# HDMI.net
KiCad netlist of a schematic drawn in Altium Designer
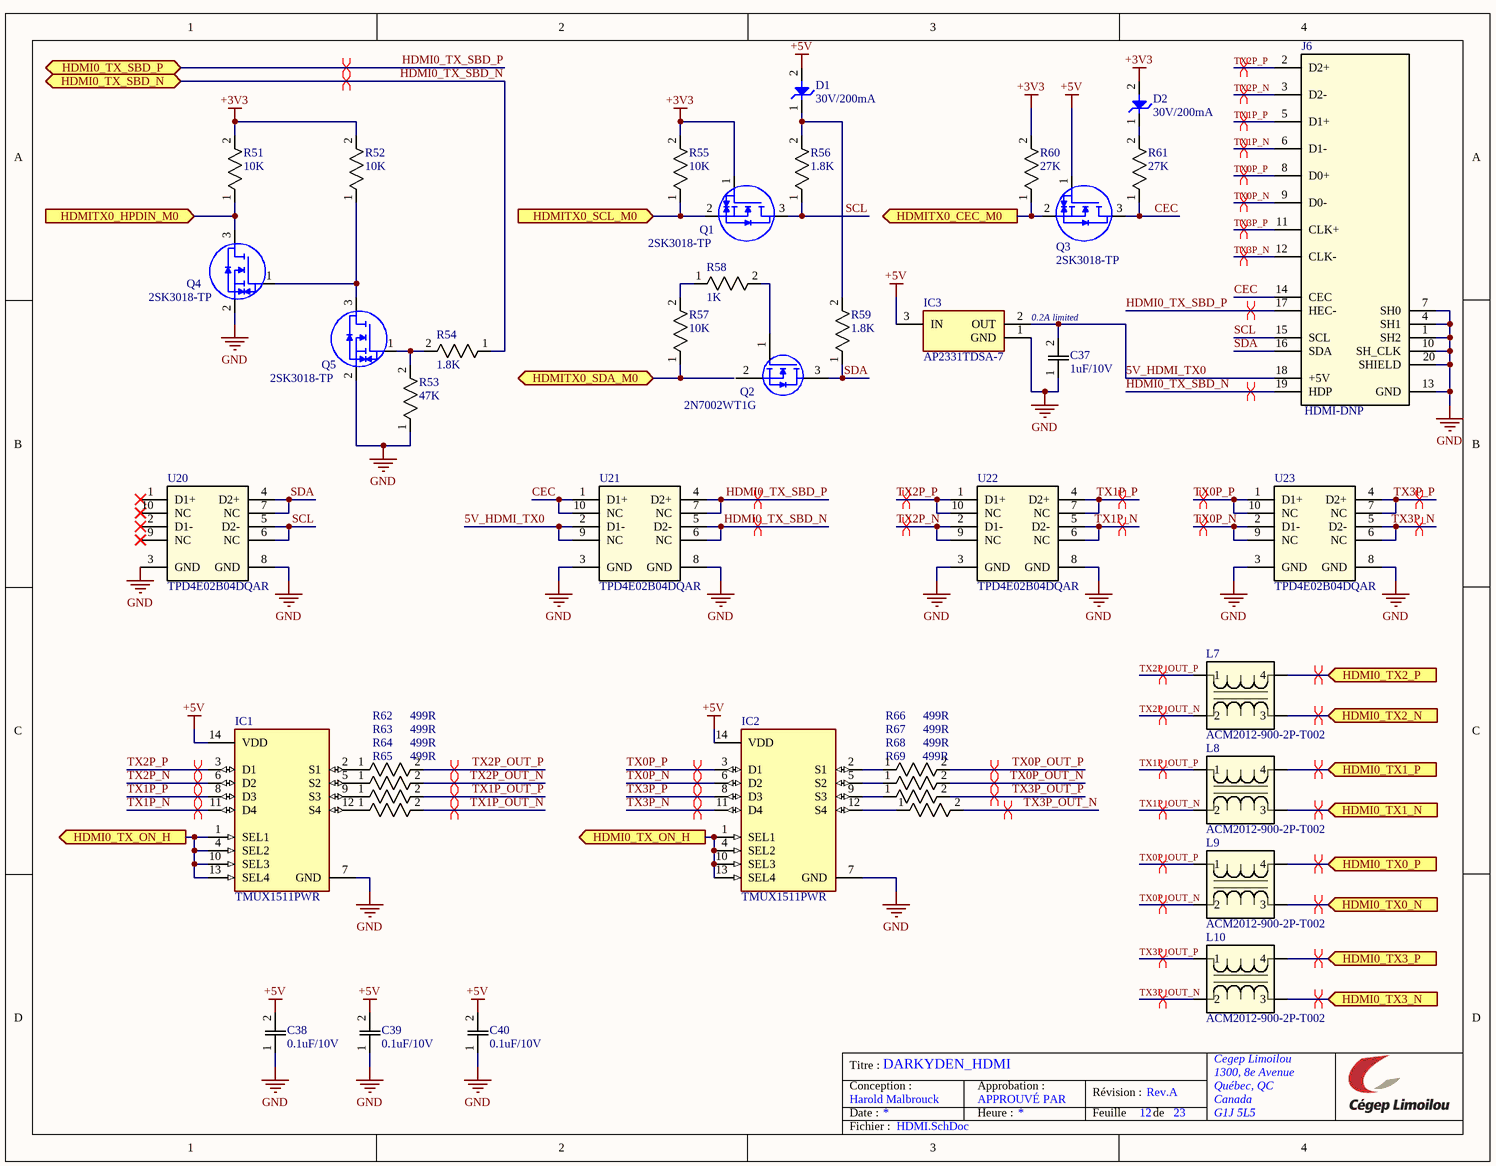
[diagram p0: HDMI.SchDoc]

(export (version "E")
  (design (tool "Eeschema 10.0.6"))
  (components
    (comp (ref "C37")
      (value "1uF/10V")
      (footprint "C0805")
      (description "Multilayer Ceramic Capacitors MLCC - SMD/SMT 10V 1uF X7R 0805 10%")
      (fields
        (field (name "MANUFACTURER") "KEMET")
        (field (name "MANUFACTURER PART NUMBER") "C0805C105K8RACTU")
      )
      (libsource (lib "DARKYDEN") (part "C0805C105K8RACTU"))
    )
    (comp (ref "C38")
      (value "0.1uF/10V")
      (footprint "c0805")
      (description "Cap Ceramic 0.1uF 10V X7R 5% Pad SMD 0805 125C T/R")
      (fields
        (field (name "MANUFACTURER") "KEMET")
        (field (name "MANUFACTURER PART NUMBER") "C0805C104J8RACTU")
      )
      (libsource (lib "DARKYDEN") (part "C0805C104J8RACTU"))
    )
    (comp (ref "C39")
      (value "0.1uF/10V")
      (footprint "c0805")
      (description "Cap Ceramic 0.1uF 10V X7R 5% Pad SMD 0805 125C T/R")
      (fields
        (field (name "MANUFACTURER") "KEMET")
        (field (name "MANUFACTURER PART NUMBER") "C0805C104J8RACTU")
      )
      (libsource (lib "DARKYDEN") (part "C0805C104J8RACTU"))
    )
    (comp (ref "C40")
      (value "0.1uF/10V")
      (footprint "c0805")
      (description "Cap Ceramic 0.1uF 10V X7R 5% Pad SMD 0805 125C T/R")
      (fields
        (field (name "MANUFACTURER") "KEMET")
        (field (name "MANUFACTURER PART NUMBER") "C0805C104J8RACTU")
      )
      (libsource (lib "DARKYDEN") (part "C0805C104J8RACTU"))
    )
    (comp (ref "D1")
      (value "30V/200mA")
      (footprint "SamacSys:SODFL1608X70N")
      (description "SCHOTTKY BARRIER DIODE Rectifier Diode, Schottky, 1 Phase, 1 Element, 0.2A, 30V V(RRM), Silicon")
      (fields
        (field (name "MANUFACTURER_PART_NUMBER") "RB521S30T1G")
        (field (name "MOUSER PART NUMBER") "863-RB521S30T1G")
      )
      (libsource (lib "SamacSys") (part "RB521S30T1G"))
    )
    (comp (ref "D2")
      (value "30V/200mA")
      (footprint "SamacSys:SODFL1608X70N")
      (description "SCHOTTKY BARRIER DIODE Rectifier Diode, Schottky, 1 Phase, 1 Element, 0.2A, 30V V(RRM), Silicon")
      (fields
        (field (name "MANUFACTURER_PART_NUMBER") "RB521S30T1G")
        (field (name "MOUSER PART NUMBER") "863-RB521S30T1G")
      )
      (libsource (lib "SamacSys") (part "RB521S30T1G"))
    )
    (comp (ref "IC1")
      (value "TMUX1511PWR")
      (footprint "SamacSys:SOP65P640X120-14N")
      (fields
        (field (name "MOUSER PART NUMBER") "595-TMUX1511PWR")
        (field (name "MANUFACTURER") "Texas Instruments")
      )
      (libsource (lib "SamacSys") (part "TMUX1511PWR"))
    )
    (comp (ref "IC2")
      (value "TMUX1511PWR")
      (footprint "SamacSys:SOP65P640X120-14N")
      (fields
        (field (name "MOUSER PART NUMBER") "595-TMUX1511PWR")
        (field (name "MANUFACTURER") "Texas Instruments")
      )
      (libsource (lib "SamacSys") (part "TMUX1511PWR"))
    )
    (comp (ref "IC3")
      (value "AP2331TDSA-7")
      (footprint "SamacSys:SOT96P240X110-3N")
      (description "USB Power Switch Single 5.2V 0.4A 3-Pin SOT-23 T/R")
      (fields (field (name "MOUSER PART NUMBER") "621-AP2331TDSA-7") (field (name "MANUFACTURER") "Diodes"))
      (libsource (lib "SamacSys") (part "AP2331TDSA-7"))
    )
    (comp (ref "J6")
      (value "HDMI-DNP")
      (footprint "HDMI_MINI")
      (description "Conn Mini HDMI PL 19 POS 0.4mm Solder RA SMD 19 Terminal 1 Port T/R")
      (fields
        (field (name "MANUFACTURER") "Wurth Electronics")
        (field (name "MANUFACTURER PART NUMBER") "685119136923")
      )
      (libsource (lib "DARKYDEN") (part "HDMI"))
    )
    (comp (ref "L7")
      (value "ACM2012-900-2P-T002")
      (footprint "SamacSys:ACM20129002PT002")
      (description "Ferrite Beads Wirewound Common Mode Filter 90Ohm 100MHz 400mA 0805 T/R")
      (fields (field (name "MOUSER PART NUMBER") "810-ACM20129002PT002") (field (name "MANUFACTURER") "TDK"))
      (libsource (lib "SamacSys") (part "ACM2012-900-2P-T002"))
    )
    (comp (ref "L8")
      (value "ACM2012-900-2P-T002")
      (footprint "SamacSys:ACM20129002PT002")
      (description "Ferrite Beads Wirewound Common Mode Filter 90Ohm 100MHz 400mA 0805 T/R")
      (fields (field (name "MOUSER PART NUMBER") "810-ACM20129002PT002") (field (name "MANUFACTURER") "TDK"))
      (libsource (lib "SamacSys") (part "ACM2012-900-2P-T002"))
    )
    (comp (ref "L9")
      (value "ACM2012-900-2P-T002")
      (footprint "SamacSys:ACM20129002PT002")
      (description "Ferrite Beads Wirewound Common Mode Filter 90Ohm 100MHz 400mA 0805 T/R")
      (fields (field (name "MOUSER PART NUMBER") "810-ACM20129002PT002") (field (name "MANUFACTURER") "TDK"))
      (libsource (lib "SamacSys") (part "ACM2012-900-2P-T002"))
    )
    (comp (ref "L10")
      (value "ACM2012-900-2P-T002")
      (footprint "SamacSys:ACM20129002PT002")
      (description "Ferrite Beads Wirewound Common Mode Filter 90Ohm 100MHz 400mA 0805 T/R")
      (fields (field (name "MOUSER PART NUMBER") "810-ACM20129002PT002") (field (name "MANUFACTURER") "TDK"))
      (libsource (lib "SamacSys") (part "ACM2012-900-2P-T002"))
    )
    (comp (ref "Q1")
      (value "2SK3018-TP")
      (footprint "SamacSys:SOT65P228X120-3N")
      (description "N-Channel 30 V 100mA (Ta) 200mW (Ta) Surface Mount SOT-323")
      (fields (field (name "MOUSER PART NUMBER") "833-2SK3018-TP"))
      (libsource (lib "SamacSys") (part "2SK3018-TP"))
    )
    (comp (ref "Q2")
      (value "2N7002WT1G")
      (footprint "SOT-323-3_2P2X1P35_ONS")
      (description "No Description Available")
      (libsource (lib "2N7002WT1G") (part "2N7002WT1G"))
    )
    (comp (ref "Q3")
      (value "2SK3018-TP")
      (footprint "SamacSys:SOT65P228X120-3N")
      (description "N-Channel 30 V 100mA (Ta) 200mW (Ta) Surface Mount SOT-323")
      (fields (field (name "MOUSER PART NUMBER") "833-2SK3018-TP"))
      (libsource (lib "SamacSys") (part "2SK3018-TP"))
    )
    (comp (ref "Q4")
      (value "2SK3018-TP")
      (footprint "SamacSys:SOT65P228X120-3N")
      (description "N-Channel 30 V 100mA (Ta) 200mW (Ta) Surface Mount SOT-323")
      (fields (field (name "MOUSER PART NUMBER") "833-2SK3018-TP"))
      (libsource (lib "SamacSys") (part "2SK3018-TP"))
    )
    (comp (ref "Q5")
      (value "2SK3018-TP")
      (footprint "SamacSys:SOT65P228X120-3N")
      (description "N-Channel 30 V 100mA (Ta) 200mW (Ta) Surface Mount SOT-323")
      (fields (field (name "MOUSER PART NUMBER") "833-2SK3018-TP"))
      (libsource (lib "SamacSys") (part "2SK3018-TP"))
    )
    (comp (ref "R51")
      (value "10K")
      (footprint "SamacSys:RESC1608X55N")
      (description "10K Ohm 5% Res Thick Film 0603  0.1W(1/10W) ±200ppm/C Pad SMD Automotive T/R")
      (fields
        (field (name "MANUFACTURER_PART_NUMBER") "ERJ-3GEYJ103V")
        (field (name "MOUSER PART NUMBER") "667-ERJ-3GEYJ103V")
      )
      (libsource (lib "DARKYDEN") (part "ERJ-3GEYJ103V"))
    )
    (comp (ref "R52")
      (value "10K")
      (footprint "SamacSys:RESC1608X55N")
      (description "10K Ohm 5% Res Thick Film 0603  0.1W(1/10W) ±200ppm/C Pad SMD Automotive T/R")
      (fields
        (field (name "MANUFACTURER_PART_NUMBER") "ERJ-3GEYJ103V")
        (field (name "MOUSER PART NUMBER") "667-ERJ-3GEYJ103V")
      )
      (libsource (lib "DARKYDEN") (part "ERJ-3GEYJ103V"))
    )
    (comp (ref "R53")
      (value "47K")
      (footprint "RESC1608X55N")
      (description "47K Ohm 5% 1/10W 0603 200ppm/C Molded SMD Punched Carrier T/R")
      (fields
        (field (name "MANUFACTURER") "Panasonic")
        (field (name "MANUFACTURER PART NUMBER") "ERJ-3GEYJ473V")
      )
      (libsource (lib "DARKYDEN") (part "ERJ-3GEYJ473V"))
    )
    (comp (ref "R54")
      (value "1.8K")
      (footprint "RESC1608X55N")
      (description "1.8 kOhm, ± 5%, 100 mW, 0603 [1608 Metric], Thick Film, General Purpose")
      (fields
        (field (name "MANUFACTURER") "Panasonic")
        (field (name "MANUFACTURER PART NUMBER") "ERJ-3GEYJ182V")
      )
      (libsource (lib "DARKYDEN") (part "ERJ-3GEYJ182V"))
    )
    (comp (ref "R55")
      (value "10K")
      (footprint "SamacSys:RESC1608X55N")
      (description "10K Ohm 5% Res Thick Film 0603  0.1W(1/10W) ±200ppm/C Pad SMD Automotive T/R")
      (fields
        (field (name "MANUFACTURER_PART_NUMBER") "ERJ-3GEYJ103V")
        (field (name "MOUSER PART NUMBER") "667-ERJ-3GEYJ103V")
      )
      (libsource (lib "DARKYDEN") (part "ERJ-3GEYJ103V"))
    )
    (comp (ref "R56")
      (value "1.8K")
      (footprint "RESC1608X55N")
      (description "1.8 kOhm, ± 5%, 100 mW, 0603 [1608 Metric], Thick Film, General Purpose")
      (fields
        (field (name "MANUFACTURER") "Panasonic")
        (field (name "MANUFACTURER PART NUMBER") "ERJ-3GEYJ182V")
      )
      (libsource (lib "DARKYDEN") (part "ERJ-3GEYJ182V"))
    )
    (comp (ref "R57")
      (value "10K")
      (footprint "SamacSys:RESC1608X55N")
      (description "10K Ohm 5% Res Thick Film 0603  0.1W(1/10W) ±200ppm/C Pad SMD Automotive T/R")
      (fields
        (field (name "MANUFACTURER_PART_NUMBER") "ERJ-3GEYJ103V")
        (field (name "MOUSER PART NUMBER") "667-ERJ-3GEYJ103V")
      )
      (libsource (lib "DARKYDEN") (part "ERJ-3GEYJ103V"))
    )
    (comp (ref "R58")
      (value "1K")
      (footprint "SamacSys:RESC1608X55N")
      (description "1K Ohm 1% 1/10W Res Thick Film 0603 ±100ppm/°C Molded SMD Punched Carrier T/R")
      (fields
        (field (name "MANUFACTURER_PART_NUMBER") "ERJ-3EKF1001V")
        (field (name "MOUSER PART NUMBER") "667-ERJ-3EKF1001V")
      )
      (libsource (lib "DARKYDEN") (part "ERJ-3EKF1001V"))
    )
    (comp (ref "R59")
      (value "1.8K")
      (footprint "RESC1608X55N")
      (description "1.8 kOhm, ± 5%, 100 mW, 0603 [1608 Metric], Thick Film, General Purpose")
      (fields
        (field (name "MANUFACTURER") "Panasonic")
        (field (name "MANUFACTURER PART NUMBER") "ERJ-3GEYJ182V")
      )
      (libsource (lib "DARKYDEN") (part "ERJ-3GEYJ182V"))
    )
    (comp (ref "R60")
      (value "27K")
      (footprint "RESC1608X55N")
      (description "27K Ohm 1% 1/10W 0603 ±100ppm/°C Molded SMD Punched Carrier T/R")
      (fields
        (field (name "MANUFACTURER") "Panasonic")
        (field (name "MANUFACTURER PART NUMBER") "ERJ-3EKF2702V")
      )
      (libsource (lib "DARKYDEN") (part "ERJ-3EKF2702V"))
    )
    (comp (ref "R61")
      (value "27K")
      (footprint "RESC1608X55N")
      (description "27K Ohm 1% 1/10W 0603 ±100ppm/°C Molded SMD Punched Carrier T/R")
      (fields
        (field (name "MANUFACTURER") "Panasonic")
        (field (name "MANUFACTURER PART NUMBER") "ERJ-3EKF2702V")
      )
      (libsource (lib "DARKYDEN") (part "ERJ-3EKF2702V"))
    )
    (comp (ref "R62")
      (value "499R")
      (footprint "RESC1608X55N")
      (description "499 Ohm, ï¿½ 1%, 100 mW, 0603 [1608 Metric], Thick Film, Precision")
      (fields
        (field (name "MANUFACTURER") "Panasonic")
        (field (name "MANUFACTURER PART NUMBER") "ERJ-3EKF4990V")
      )
      (libsource (lib "DARKYDEN") (part "ERJ-3EKF4990V"))
    )
    (comp (ref "R63")
      (value "499R")
      (footprint "RESC1608X55N")
      (description "499 Ohm, ï¿½ 1%, 100 mW, 0603 [1608 Metric], Thick Film, Precision")
      (fields
        (field (name "MANUFACTURER") "Panasonic")
        (field (name "MANUFACTURER PART NUMBER") "ERJ-3EKF4990V")
      )
      (libsource (lib "DARKYDEN") (part "ERJ-3EKF4990V"))
    )
    (comp (ref "R64")
      (value "499R")
      (footprint "RESC1608X55N")
      (description "499 Ohm, ï¿½ 1%, 100 mW, 0603 [1608 Metric], Thick Film, Precision")
      (fields
        (field (name "MANUFACTURER") "Panasonic")
        (field (name "MANUFACTURER PART NUMBER") "ERJ-3EKF4990V")
      )
      (libsource (lib "DARKYDEN") (part "ERJ-3EKF4990V"))
    )
    (comp (ref "R65")
      (value "499R")
      (footprint "RESC1608X55N")
      (description "499 Ohm, ï¿½ 1%, 100 mW, 0603 [1608 Metric], Thick Film, Precision")
      (fields
        (field (name "MANUFACTURER") "Panasonic")
        (field (name "MANUFACTURER PART NUMBER") "ERJ-3EKF4990V")
      )
      (libsource (lib "DARKYDEN") (part "ERJ-3EKF4990V"))
    )
    (comp (ref "R66")
      (value "499R")
      (footprint "RESC1608X55N")
      (description "499 Ohm, ï¿½ 1%, 100 mW, 0603 [1608 Metric], Thick Film, Precision")
      (fields
        (field (name "MANUFACTURER") "Panasonic")
        (field (name "MANUFACTURER PART NUMBER") "ERJ-3EKF4990V")
      )
      (libsource (lib "DARKYDEN") (part "ERJ-3EKF4990V"))
    )
    (comp (ref "R67")
      (value "499R")
      (footprint "RESC1608X55N")
      (description "499 Ohm, ï¿½ 1%, 100 mW, 0603 [1608 Metric], Thick Film, Precision")
      (fields
        (field (name "MANUFACTURER") "Panasonic")
        (field (name "MANUFACTURER PART NUMBER") "ERJ-3EKF4990V")
      )
      (libsource (lib "DARKYDEN") (part "ERJ-3EKF4990V"))
    )
    (comp (ref "R68")
      (value "499R")
      (footprint "RESC1608X55N")
      (description "499 Ohm, ï¿½ 1%, 100 mW, 0603 [1608 Metric], Thick Film, Precision")
      (fields
        (field (name "MANUFACTURER") "Panasonic")
        (field (name "MANUFACTURER PART NUMBER") "ERJ-3EKF4990V")
      )
      (libsource (lib "DARKYDEN") (part "ERJ-3EKF4990V"))
    )
    (comp (ref "R69")
      (value "499R")
      (footprint "RESC1608X55N")
      (description "499 Ohm, ï¿½ 1%, 100 mW, 0603 [1608 Metric], Thick Film, Precision")
      (fields
        (field (name "MANUFACTURER") "Panasonic")
        (field (name "MANUFACTURER PART NUMBER") "ERJ-3EKF4990V")
      )
      (libsource (lib "DARKYDEN") (part "ERJ-3EKF4990V"))
    )
    (comp (ref "U20")
      (value "TPD4E02B04DQAR")
      (footprint "DQA0010A")
      (description "TVS DIODE 3.6V 8.8V 10USON / 4-Channel ESD Protection Diode for USB Type-C and HDMI 2.0")
      (fields (field (name "MANUFACTURER") "Texas Instruments"))
      (libsource (lib "TPD4E02B04DQAR") (part "TPD4E02B04DQAR"))
    )
    (comp (ref "U21")
      (value "TPD4E02B04DQAR")
      (footprint "DQA0010A")
      (description "TVS DIODE 3.6V 8.8V 10USON / 4-Channel ESD Protection Diode for USB Type-C and HDMI 2.0")
      (fields (field (name "MANUFACTURER") "Texas Instruments"))
      (libsource (lib "TPD4E02B04DQAR") (part "TPD4E02B04DQAR"))
    )
    (comp (ref "U22")
      (value "TPD4E02B04DQAR")
      (footprint "DQA0010A")
      (description "TVS DIODE 3.6V 8.8V 10USON / 4-Channel ESD Protection Diode for USB Type-C and HDMI 2.0")
      (fields (field (name "MANUFACTURER") "Texas Instruments"))
      (libsource (lib "TPD4E02B04DQAR") (part "TPD4E02B04DQAR"))
    )
    (comp (ref "U23")
      (value "TPD4E02B04DQAR")
      (footprint "DQA0010A")
      (description "TVS DIODE 3.6V 8.8V 10USON / 4-Channel ESD Protection Diode for USB Type-C and HDMI 2.0")
      (fields (field (name "MANUFACTURER") "Texas Instruments"))
      (libsource (lib "TPD4E02B04DQAR") (part "TPD4E02B04DQAR"))
    )
  )
  (nets
    (net (code "1") (name "+3V3") (class "Default")
      (node (ref "D2") (pin "2") (pinfunction "A_2") (pintype "passive"))
      (node (ref "Q1") (pin "1") (pinfunction "G_1") (pintype "passive"))
      (node (ref "R51") (pin "2") (pinfunction "2_2") (pintype "passive"))
      (node (ref "R52") (pin "2") (pinfunction "2_2") (pintype "passive"))
      (node (ref "R55") (pin "2") (pinfunction "2_2") (pintype "passive"))
      (node (ref "R60") (pin "2") (pinfunction "2_2") (pintype "passive"))
    )
    (net (code "2") (name "+5V") (class "Default")
      (node (ref "C38") (pin "2") (pinfunction "2_2") (pintype "passive"))
      (node (ref "C39") (pin "2") (pinfunction "2_2") (pintype "passive"))
      (node (ref "C40") (pin "2") (pinfunction "2_2") (pintype "passive"))
      (node (ref "D1") (pin "2") (pinfunction "A_2") (pintype "passive"))
      (node (ref "IC1") (pin "14") (pinfunction "VDD_14") (pintype "power_in"))
      (node (ref "IC2") (pin "14") (pinfunction "VDD_14") (pintype "power_in"))
      (node (ref "IC3") (pin "3") (pinfunction "IN_3") (pintype "passive"))
      (node (ref "Q3") (pin "1") (pinfunction "G_1") (pintype "passive"))
    )
    (net (code "3") (name "/5V_HDMI_TX0") (class "Default")
      (node (ref "C37") (pin "2") (pinfunction "2_2") (pintype "passive"))
      (node (ref "IC3") (pin "2") (pinfunction "OUT_2") (pintype "passive"))
      (node (ref "J6") (pin "18") (pinfunction "+5V_18") (pintype "passive"))
      (node (ref "U21") (pin "2") (pinfunction "D1-_2") (pintype "passive"))
      (node (ref "U21") (pin "9") (pinfunction "NC_9") (pintype "passive"))
    )
    (net (code "4") (name "/CEC") (class "Default")
      (node (ref "J6") (pin "14") (pinfunction "CEC_14") (pintype "passive"))
      (node (ref "Q3") (pin "3") (pinfunction "D_3") (pintype "passive"))
      (node (ref "R61") (pin "1") (pinfunction "1_1") (pintype "passive"))
      (node (ref "U21") (pin "1") (pinfunction "D1+_1") (pintype "passive"))
      (node (ref "U21") (pin "10") (pinfunction "NC_10") (pintype "passive"))
    )
    (net (code "5") (name "/HDMI0_TX0_N") (class "Default")
      (node (ref "L9") (pin "3") (pinfunction "3_3") (pintype "passive"))
    )
    (net (code "6") (name "/HDMI0_TX0_P") (class "Default")
      (node (ref "L9") (pin "4") (pinfunction "4_4") (pintype "passive"))
    )
    (net (code "7") (name "/HDMI0_TX1_N") (class "Default")
      (node (ref "L8") (pin "3") (pinfunction "3_3") (pintype "passive"))
    )
    (net (code "8") (name "/HDMI0_TX1_P") (class "Default")
      (node (ref "L8") (pin "4") (pinfunction "4_4") (pintype "passive"))
    )
    (net (code "9") (name "/HDMI0_TX2_N") (class "Default")
      (node (ref "L7") (pin "3") (pinfunction "3_3") (pintype "passive"))
    )
    (net (code "10") (name "/HDMI0_TX2_P") (class "Default")
      (node (ref "L7") (pin "4") (pinfunction "4_4") (pintype "passive"))
    )
    (net (code "11") (name "/HDMI0_TX3_N") (class "Default")
      (node (ref "L10") (pin "3") (pinfunction "3_3") (pintype "passive"))
    )
    (net (code "12") (name "/HDMI0_TX3_P") (class "Default")
      (node (ref "L10") (pin "4") (pinfunction "4_4") (pintype "passive"))
    )
    (net (code "13") (name "/HDMI0_TX_ON_H") (class "Default")
      (node (ref "IC1") (pin "1") (pinfunction "SEL1_1") (pintype "input"))
      (node (ref "IC1") (pin "10") (pinfunction "SEL3_10") (pintype "input"))
      (node (ref "IC1") (pin "13") (pinfunction "SEL4_13") (pintype "input"))
      (node (ref "IC1") (pin "4") (pinfunction "SEL2_4") (pintype "input"))
      (node (ref "IC2") (pin "1") (pinfunction "SEL1_1") (pintype "input"))
      (node (ref "IC2") (pin "10") (pinfunction "SEL3_10") (pintype "input"))
      (node (ref "IC2") (pin "13") (pinfunction "SEL4_13") (pintype "input"))
      (node (ref "IC2") (pin "4") (pinfunction "SEL2_4") (pintype "input"))
    )
    (net (code "14") (name "/HDMI0_TX_SBD_N") (class "Default")
      (node (ref "J6") (pin "19") (pinfunction "HDP_19") (pintype "passive"))
      (node (ref "R54") (pin "1") (pinfunction "1_1") (pintype "passive"))
      (node (ref "U21") (pin "5") (pinfunction "D2-_5") (pintype "passive"))
      (node (ref "U21") (pin "6") (pinfunction "NC_6") (pintype "passive"))
    )
    (net (code "15") (name "/HDMI0_TX_SBD_P") (class "Default")
      (node (ref "J6") (pin "17") (pinfunction "HEC-_17") (pintype "passive"))
      (node (ref "U21") (pin "4") (pinfunction "D2+_4") (pintype "passive"))
      (node (ref "U21") (pin "7") (pinfunction "NC_7") (pintype "passive"))
    )
    (net (code "16") (name "/HDMITX0_CEC_M0") (class "Default")
      (node (ref "Q3") (pin "2") (pinfunction "S_2") (pintype "passive"))
      (node (ref "R60") (pin "1") (pinfunction "1_1") (pintype "passive"))
    )
    (net (code "17") (name "/HDMITX0_HPDIN_M0") (class "Default")
      (node (ref "Q4") (pin "3") (pinfunction "D_3") (pintype "passive"))
      (node (ref "R51") (pin "1") (pinfunction "1_1") (pintype "passive"))
    )
    (net (code "18") (name "/HDMITX0_SCL_M0") (class "Default")
      (node (ref "Q1") (pin "2") (pinfunction "S_2") (pintype "passive"))
      (node (ref "R55") (pin "1") (pinfunction "1_1") (pintype "passive"))
    )
    (net (code "19") (name "/HDMITX0_SDA_M0") (class "Default")
      (node (ref "R57") (pin "1") (pinfunction "1_1") (pintype "passive"))
    )
    (net (code "20") (name "/SCL") (class "Default")
      (node (ref "J6") (pin "15") (pinfunction "SCL_15") (pintype "passive"))
      (node (ref "Q1") (pin "3") (pinfunction "D_3") (pintype "passive"))
      (node (ref "R56") (pin "1") (pinfunction "1_1") (pintype "passive"))
      (node (ref "U20") (pin "5") (pinfunction "D2-_5") (pintype "passive"))
      (node (ref "U20") (pin "6") (pinfunction "NC_6") (pintype "passive"))
    )
    (net (code "21") (name "/SDA") (class "Default")
      (node (ref "J6") (pin "16") (pinfunction "SDA_16") (pintype "passive"))
      (node (ref "Q2") (pin "3") (pinfunction "DRAIN_3") (pintype "passive"))
      (node (ref "R59") (pin "1") (pinfunction "1_1") (pintype "passive"))
      (node (ref "U20") (pin "4") (pinfunction "D2+_4") (pintype "passive"))
      (node (ref "U20") (pin "7") (pinfunction "NC_7") (pintype "passive"))
    )
    (net (code "22") (name "/TX0P_N") (class "Default")
      (node (ref "IC2") (pin "6") (pinfunction "D2_6") (pintype "bidirectional"))
      (node (ref "J6") (pin "9") (pinfunction "D0-_9") (pintype "passive"))
      (node (ref "U23") (pin "2") (pinfunction "D1-_2") (pintype "passive"))
      (node (ref "U23") (pin "9") (pinfunction "NC_9") (pintype "passive"))
    )
    (net (code "23") (name "/TX0P_OUT_N") (class "Default")
      (node (ref "L9") (pin "2") (pinfunction "2_2") (pintype "passive"))
      (node (ref "R67") (pin "2") (pinfunction "2_2") (pintype "passive"))
    )
    (net (code "24") (name "/TX0P_OUT_P") (class "Default")
      (node (ref "L9") (pin "1") (pinfunction "1_1") (pintype "passive"))
      (node (ref "R66") (pin "2") (pinfunction "2_2") (pintype "passive"))
    )
    (net (code "25") (name "/TX0P_P") (class "Default")
      (node (ref "IC2") (pin "3") (pinfunction "D1_3") (pintype "bidirectional"))
      (node (ref "J6") (pin "8") (pinfunction "D0+_8") (pintype "passive"))
      (node (ref "U23") (pin "1") (pinfunction "D1+_1") (pintype "passive"))
      (node (ref "U23") (pin "10") (pinfunction "NC_10") (pintype "passive"))
    )
    (net (code "26") (name "/TX1P_N") (class "Default")
      (node (ref "IC1") (pin "11") (pinfunction "D4_11") (pintype "bidirectional"))
      (node (ref "J6") (pin "6") (pinfunction "D1-_6") (pintype "passive"))
      (node (ref "U22") (pin "5") (pinfunction "D2-_5") (pintype "passive"))
      (node (ref "U22") (pin "6") (pinfunction "NC_6") (pintype "passive"))
    )
    (net (code "27") (name "/TX1P_OUT_N") (class "Default")
      (node (ref "L8") (pin "2") (pinfunction "2_2") (pintype "passive"))
      (node (ref "R65") (pin "2") (pinfunction "2_2") (pintype "passive"))
    )
    (net (code "28") (name "/TX1P_OUT_P") (class "Default")
      (node (ref "L8") (pin "1") (pinfunction "1_1") (pintype "passive"))
      (node (ref "R64") (pin "2") (pinfunction "2_2") (pintype "passive"))
    )
    (net (code "29") (name "/TX1P_P") (class "Default")
      (node (ref "IC1") (pin "8") (pinfunction "D3_8") (pintype "bidirectional"))
      (node (ref "J6") (pin "5") (pinfunction "D1+_5") (pintype "passive"))
      (node (ref "U22") (pin "4") (pinfunction "D2+_4") (pintype "passive"))
      (node (ref "U22") (pin "7") (pinfunction "NC_7") (pintype "passive"))
    )
    (net (code "30") (name "/TX2P_N") (class "Default")
      (node (ref "IC1") (pin "6") (pinfunction "D2_6") (pintype "bidirectional"))
      (node (ref "J6") (pin "3") (pinfunction "D2-_3") (pintype "passive"))
      (node (ref "U22") (pin "2") (pinfunction "D1-_2") (pintype "passive"))
      (node (ref "U22") (pin "9") (pinfunction "NC_9") (pintype "passive"))
    )
    (net (code "31") (name "/TX2P_OUT_N") (class "Default")
      (node (ref "L7") (pin "2") (pinfunction "2_2") (pintype "passive"))
      (node (ref "R63") (pin "2") (pinfunction "2_2") (pintype "passive"))
    )
    (net (code "32") (name "/TX2P_OUT_P") (class "Default")
      (node (ref "L7") (pin "1") (pinfunction "1_1") (pintype "passive"))
      (node (ref "R62") (pin "2") (pinfunction "2_2") (pintype "passive"))
    )
    (net (code "33") (name "/TX2P_P") (class "Default")
      (node (ref "IC1") (pin "3") (pinfunction "D1_3") (pintype "bidirectional"))
      (node (ref "J6") (pin "2") (pinfunction "D2+_2") (pintype "passive"))
      (node (ref "U22") (pin "1") (pinfunction "D1+_1") (pintype "passive"))
      (node (ref "U22") (pin "10") (pinfunction "NC_10") (pintype "passive"))
    )
    (net (code "34") (name "/TX3P_N") (class "Default")
      (node (ref "IC2") (pin "11") (pinfunction "D4_11") (pintype "bidirectional"))
      (node (ref "J6") (pin "12") (pinfunction "CLK-_12") (pintype "passive"))
      (node (ref "U23") (pin "5") (pinfunction "D2-_5") (pintype "passive"))
      (node (ref "U23") (pin "6") (pinfunction "NC_6") (pintype "passive"))
    )
    (net (code "35") (name "/TX3P_OUT_N") (class "Default")
      (node (ref "L10") (pin "2") (pinfunction "2_2") (pintype "passive"))
      (node (ref "R69") (pin "2") (pinfunction "2_2") (pintype "passive"))
    )
    (net (code "36") (name "/TX3P_OUT_P") (class "Default")
      (node (ref "L10") (pin "1") (pinfunction "1_1") (pintype "passive"))
      (node (ref "R68") (pin "2") (pinfunction "2_2") (pintype "passive"))
    )
    (net (code "37") (name "/TX3P_P") (class "Default")
      (node (ref "IC2") (pin "8") (pinfunction "D3_8") (pintype "bidirectional"))
      (node (ref "J6") (pin "11") (pinfunction "CLK+_11") (pintype "passive"))
      (node (ref "U23") (pin "4") (pinfunction "D2+_4") (pintype "passive"))
      (node (ref "U23") (pin "7") (pinfunction "NC_7") (pintype "passive"))
    )
    (net (code "38") (name "GND") (class "Default")
      (node (ref "C37") (pin "1") (pinfunction "1_1") (pintype "passive"))
      (node (ref "C38") (pin "1") (pinfunction "1_1") (pintype "passive"))
      (node (ref "C39") (pin "1") (pinfunction "1_1") (pintype "passive"))
      (node (ref "C40") (pin "1") (pinfunction "1_1") (pintype "passive"))
      (node (ref "IC1") (pin "7") (pinfunction "GND_7") (pintype "power_in"))
      (node (ref "IC2") (pin "7") (pinfunction "GND_7") (pintype "power_in"))
      (node (ref "IC3") (pin "1") (pinfunction "GND_1") (pintype "passive"))
      (node (ref "J6") (pin "1") (pinfunction "SH2_1") (pintype "passive"))
      (node (ref "J6") (pin "10") (pinfunction "SH_CLK_10") (pintype "passive"))
      (node (ref "J6") (pin "13") (pinfunction "GND_13") (pintype "passive"))
      (node (ref "J6") (pin "20") (pinfunction "SHIELD_20") (pintype "passive"))
      (node (ref "J6") (pin "4") (pinfunction "SH1_4") (pintype "passive"))
      (node (ref "J6") (pin "7") (pinfunction "SH0_7") (pintype "passive"))
      (node (ref "Q4") (pin "2") (pinfunction "S_2") (pintype "passive"))
      (node (ref "Q5") (pin "2") (pinfunction "S_2") (pintype "passive"))
      (node (ref "R53") (pin "1") (pinfunction "1_1") (pintype "passive"))
      (node (ref "U20") (pin "3") (pinfunction "GND_3") (pintype "passive"))
      (node (ref "U20") (pin "8") (pinfunction "GND_8") (pintype "passive"))
      (node (ref "U21") (pin "3") (pinfunction "GND_3") (pintype "passive"))
      (node (ref "U21") (pin "8") (pinfunction "GND_8") (pintype "passive"))
      (node (ref "U22") (pin "3") (pinfunction "GND_3") (pintype "passive"))
      (node (ref "U22") (pin "8") (pinfunction "GND_8") (pintype "passive"))
      (node (ref "U23") (pin "3") (pinfunction "GND_3") (pintype "passive"))
      (node (ref "U23") (pin "8") (pinfunction "GND_8") (pintype "passive"))
    )
    (net (code "39") (name "Net-(D1-K)") (class "Default")
      (node (ref "D1") (pin "1") (pinfunction "K_1") (pintype "passive"))
      (node (ref "R56") (pin "2") (pinfunction "2_2") (pintype "passive"))
      (node (ref "R59") (pin "2") (pinfunction "2_2") (pintype "passive"))
    )
    (net (code "40") (name "Net-(D2-K)") (class "Default")
      (node (ref "D2") (pin "1") (pinfunction "K_1") (pintype "passive"))
      (node (ref "R61") (pin "2") (pinfunction "2_2") (pintype "passive"))
    )
    (net (code "41") (name "Net-(IC1-S1)") (class "Default")
      (node (ref "IC1") (pin "2") (pinfunction "S1_2") (pintype "bidirectional"))
      (node (ref "R62") (pin "1") (pinfunction "1_1") (pintype "passive"))
    )
    (net (code "42") (name "Net-(IC1-S2)") (class "Default")
      (node (ref "IC1") (pin "5") (pinfunction "S2_5") (pintype "bidirectional"))
      (node (ref "R63") (pin "1") (pinfunction "1_1") (pintype "passive"))
    )
    (net (code "43") (name "Net-(IC1-S3)") (class "Default")
      (node (ref "IC1") (pin "9") (pinfunction "S3_9") (pintype "bidirectional"))
      (node (ref "R64") (pin "1") (pinfunction "1_1") (pintype "passive"))
    )
    (net (code "44") (name "Net-(IC1-S4)") (class "Default")
      (node (ref "IC1") (pin "12") (pinfunction "S4_12") (pintype "bidirectional"))
      (node (ref "R65") (pin "1") (pinfunction "1_1") (pintype "passive"))
    )
    (net (code "45") (name "Net-(IC2-S1)") (class "Default")
      (node (ref "IC2") (pin "2") (pinfunction "S1_2") (pintype "bidirectional"))
      (node (ref "R66") (pin "1") (pinfunction "1_1") (pintype "passive"))
    )
    (net (code "46") (name "Net-(IC2-S2)") (class "Default")
      (node (ref "IC2") (pin "5") (pinfunction "S2_5") (pintype "bidirectional"))
      (node (ref "R67") (pin "1") (pinfunction "1_1") (pintype "passive"))
    )
    (net (code "47") (name "Net-(IC2-S3)") (class "Default")
      (node (ref "IC2") (pin "9") (pinfunction "S3_9") (pintype "bidirectional"))
      (node (ref "R68") (pin "1") (pinfunction "1_1") (pintype "passive"))
    )
    (net (code "48") (name "Net-(IC2-S4)") (class "Default")
      (node (ref "IC2") (pin "12") (pinfunction "S4_12") (pintype "bidirectional"))
      (node (ref "R69") (pin "1") (pinfunction "1_1") (pintype "passive"))
    )
    (net (code "49") (name "Net-(Q2-GATE)") (class "Default")
      (node (ref "Q2") (pin "1") (pinfunction "GATE_1") (pintype "passive"))
      (node (ref "R58") (pin "2") (pinfunction "2_2") (pintype "passive"))
    )
    (net (code "50") (name "Net-(Q4-G)") (class "Default")
      (node (ref "Q4") (pin "1") (pinfunction "G_1") (pintype "passive"))
      (node (ref "Q5") (pin "3") (pinfunction "D_3") (pintype "passive"))
      (node (ref "R52") (pin "1") (pinfunction "1_1") (pintype "passive"))
    )
    (net (code "51") (name "Net-(Q5-G)") (class "Default")
      (node (ref "Q5") (pin "1") (pinfunction "G_1") (pintype "passive"))
      (node (ref "R53") (pin "2") (pinfunction "2_2") (pintype "passive"))
      (node (ref "R54") (pin "2") (pinfunction "2_2") (pintype "passive"))
    )
    (net (code "52") (name "Net-(R57-Pad2)") (class "Default")
      (node (ref "R57") (pin "2") (pinfunction "2_2") (pintype "passive"))
      (node (ref "R58") (pin "1") (pinfunction "1_1") (pintype "passive"))
    )
    (net (code "53") (name "unconnected-(Q2-SOURCE-Pad2)") (class "Default")
      (node (ref "Q2") (pin "2") (pinfunction "SOURCE_2") (pintype "passive"))
    )
    (net (code "54") (name "unconnected-(U20-D1+-Pad1)") (class "Default")
      (node (ref "U20") (pin "1") (pinfunction "D1+_1") (pintype "passive+no_connect"))
    )
    (net (code "55") (name "unconnected-(U20-D1--Pad2)") (class "Default")
      (node (ref "U20") (pin "2") (pinfunction "D1-_2") (pintype "passive+no_connect"))
    )
    (net (code "56") (name "unconnected-(U20-NC-Pad9)") (class "Default")
      (node (ref "U20") (pin "9") (pinfunction "NC_9") (pintype "passive+no_connect"))
    )
    (net (code "57") (name "unconnected-(U20-NC-Pad10)") (class "Default")
      (node (ref "U20") (pin "10") (pinfunction "NC_10") (pintype "passive+no_connect"))
    )
  )
)
